# ProPrj_USB_Hub_Port_PCB_2026-08-16.net
KiCad netlist of a schematic drawn in EasyEDA Pro
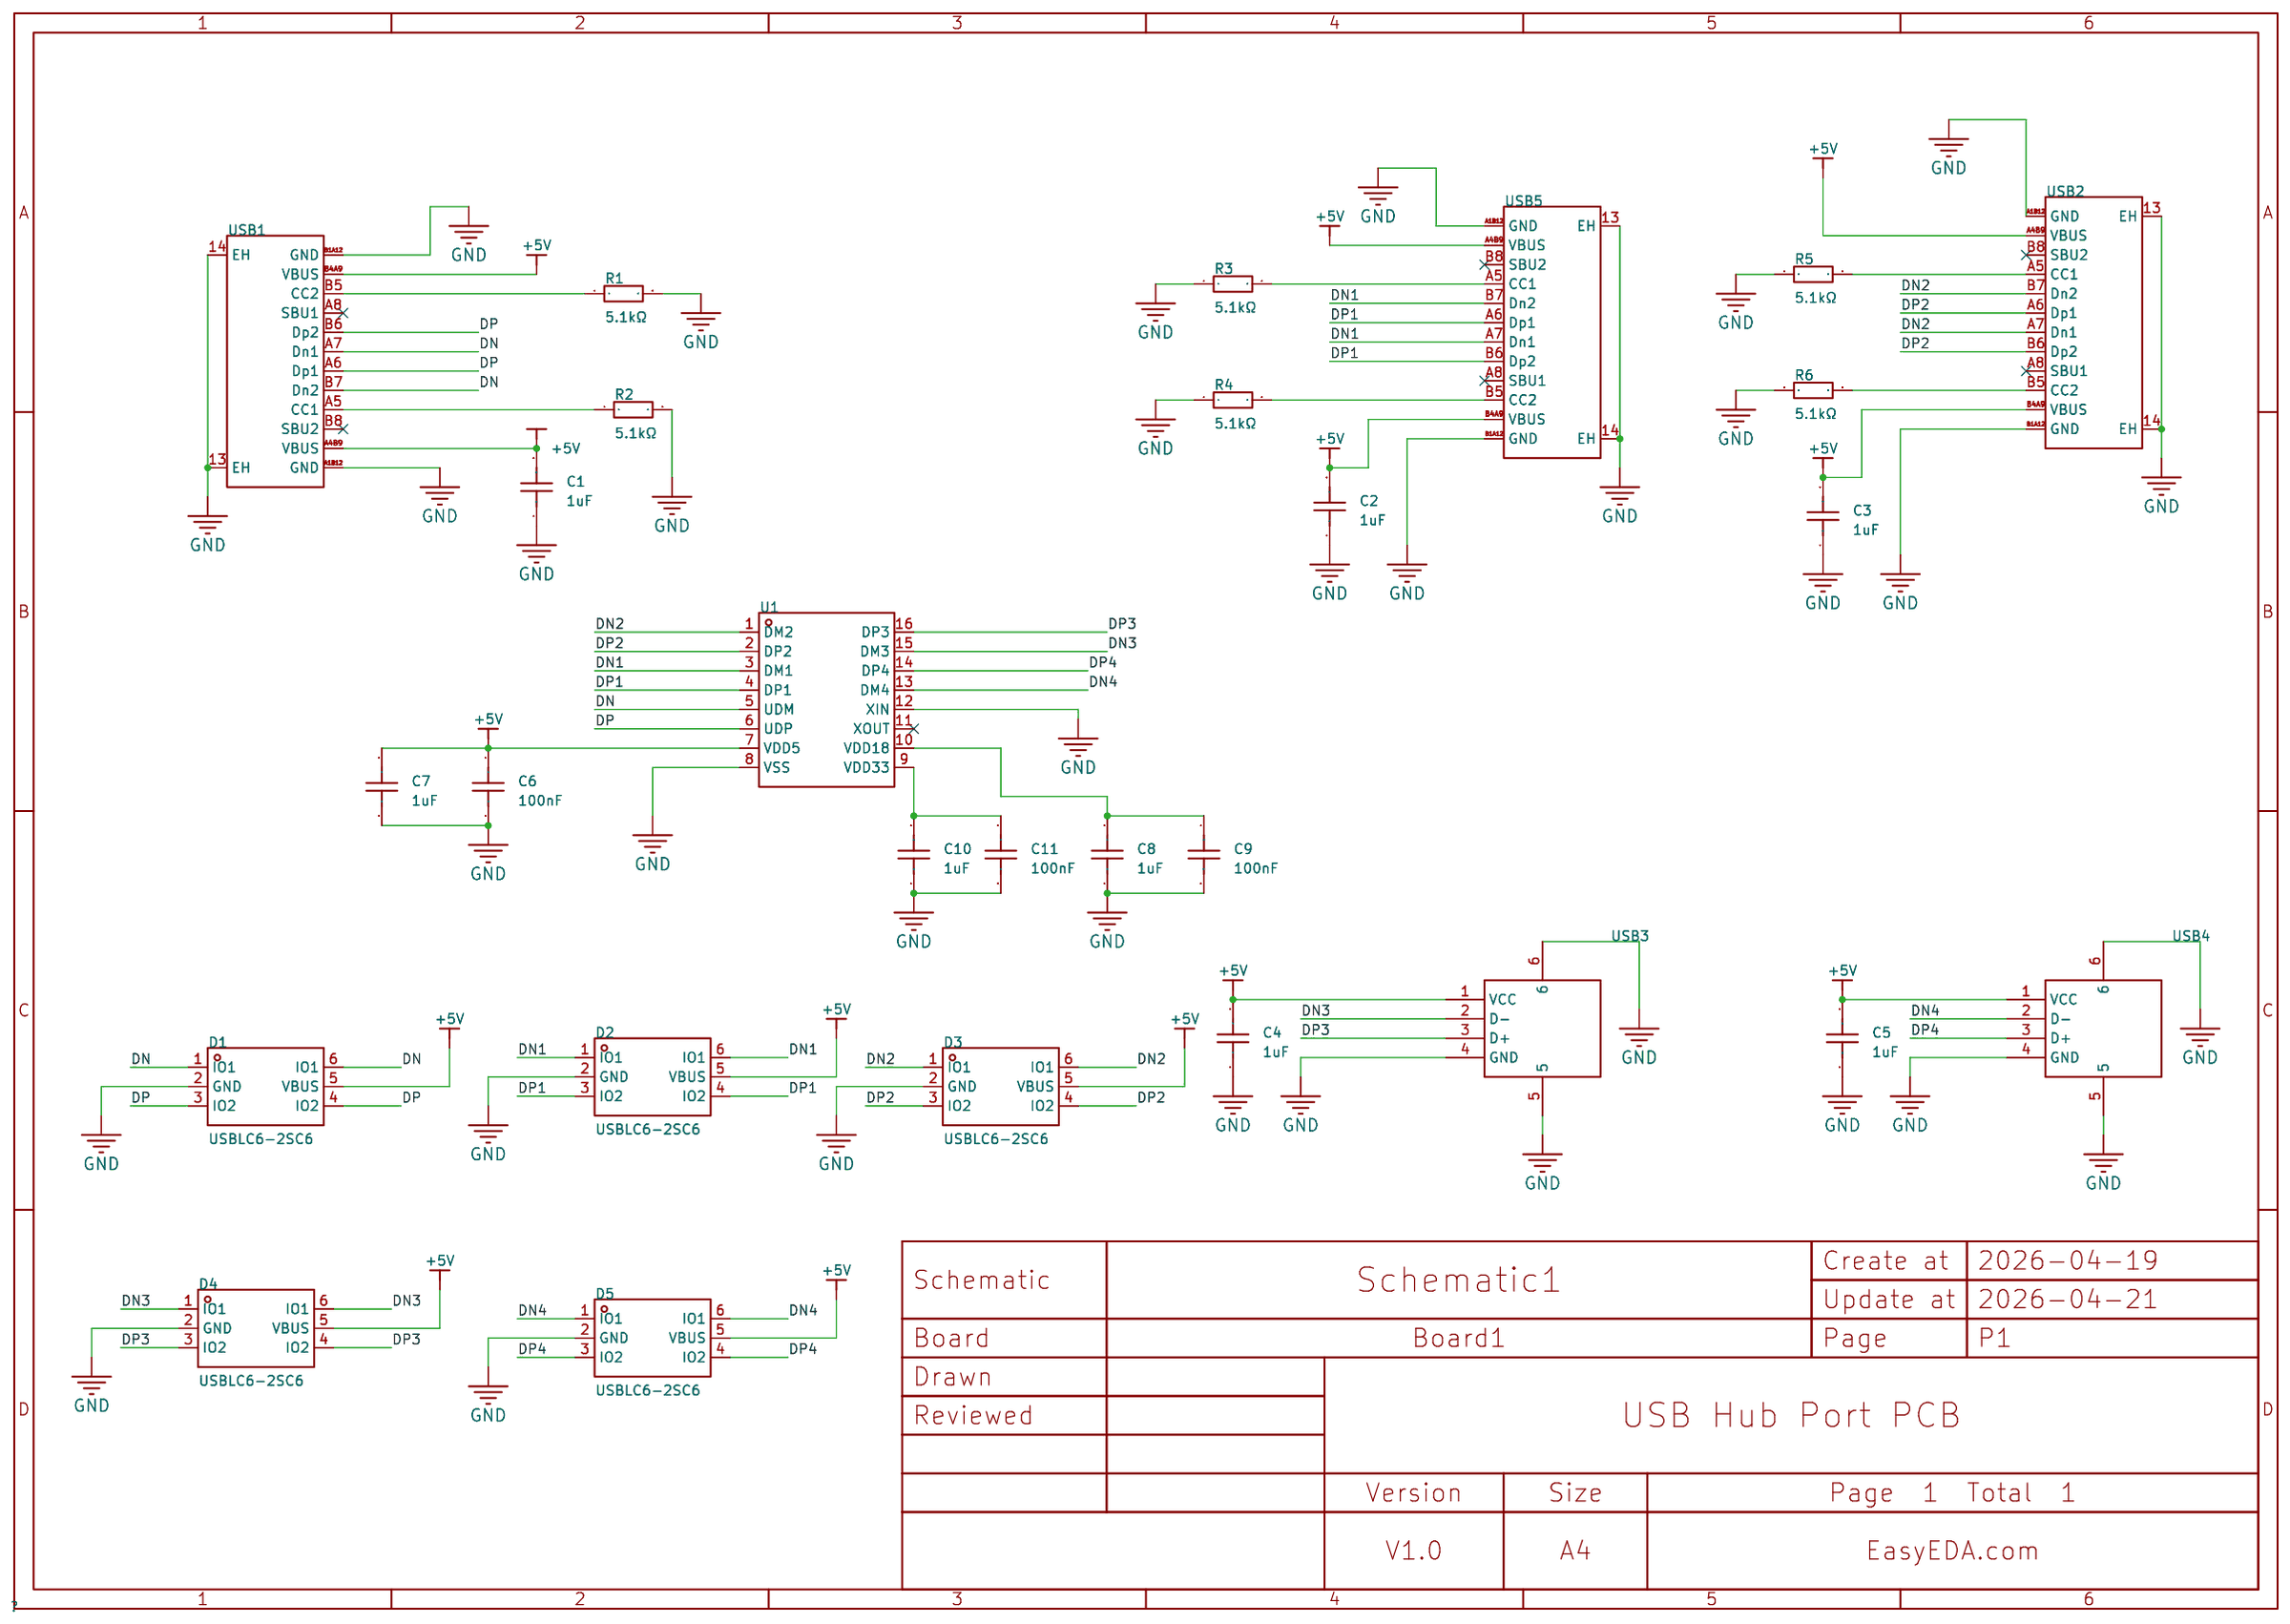
[diagram p0: schematic sheet]

(export (version "E")
  (design (tool "Eeschema 10.0.6"))
  (components
    (comp (ref "C1")
      (value "1uF")
      (footprint "easyedapro:C0603")
      (description "Capacitance:1uF Tolerance:±10% Tolerance:±10% Voltage Rating:50V Temperature Coefficient:X5R")
      (fields
        (field (name "Manufacturer Part") "CL10A105KB8NNNC")
        (field (name "Manufacturer") "SAMSUNG(三星)")
      )
      (libsource (lib "easyedapro") (part "CL10A105KB8NNNC"))
    )
    (comp (ref "C2")
      (value "1uF")
      (footprint "easyedapro:C0603")
      (description "Capacitance:1uF Tolerance:±10% Tolerance:±10% Voltage Rating:50V Temperature Coefficient:X5R")
      (fields
        (field (name "Manufacturer Part") "CL10A105KB8NNNC")
        (field (name "Manufacturer") "SAMSUNG(三星)")
      )
      (libsource (lib "easyedapro") (part "CL10A105KB8NNNC"))
    )
    (comp (ref "C3")
      (value "1uF")
      (footprint "easyedapro:C0603")
      (description "Capacitance:1uF Tolerance:±10% Tolerance:±10% Voltage Rating:50V Temperature Coefficient:X5R")
      (fields
        (field (name "Manufacturer Part") "CL10A105KB8NNNC")
        (field (name "Manufacturer") "SAMSUNG(三星)")
      )
      (libsource (lib "easyedapro") (part "CL10A105KB8NNNC"))
    )
    (comp (ref "C4")
      (value "1uF")
      (footprint "easyedapro:C0603")
      (description "Capacitance:1uF Tolerance:±10% Tolerance:±10% Voltage Rating:50V Temperature Coefficient:X5R")
      (fields
        (field (name "Manufacturer Part") "CL10A105KB8NNNC")
        (field (name "Manufacturer") "SAMSUNG(三星)")
      )
      (libsource (lib "easyedapro") (part "CL10A105KB8NNNC"))
    )
    (comp (ref "C5")
      (value "1uF")
      (footprint "easyedapro:C0603")
      (description "Capacitance:1uF Tolerance:±10% Tolerance:±10% Voltage Rating:50V Temperature Coefficient:X5R")
      (fields
        (field (name "Manufacturer Part") "CL10A105KB8NNNC")
        (field (name "Manufacturer") "SAMSUNG(三星)")
      )
      (libsource (lib "easyedapro") (part "CL10A105KB8NNNC"))
    )
    (comp (ref "C6")
      (value "100nF")
      (footprint "easyedapro:CAP-TH_L7.4-W2.3-P5.08-D0.6")
      (description "Capacitance:100nF Tolerance:±10% Tolerance:±10% Voltage Rating:50V Temperature Coefficient:X7R")
      (fields
        (field (name "Manufacturer Part") "CL10B104KB8NNNC")
        (field (name "Manufacturer") "SAMSUNG(三星)")
      )
      (libsource (lib "easyedapro") (part "CAPR500-350X720X850100NF100V"))
    )
    (comp (ref "C7")
      (value "1uF")
      (footprint "easyedapro:C0603")
      (description "Capacitance:1uF Tolerance:±10% Tolerance:±10% Voltage Rating:50V Temperature Coefficient:X5R")
      (fields
        (field (name "Manufacturer Part") "CL10A105KB8NNNC")
        (field (name "Manufacturer") "SAMSUNG(三星)")
      )
      (libsource (lib "easyedapro") (part "CL10A105KB8NNNC"))
    )
    (comp (ref "C8")
      (value "1uF")
      (footprint "easyedapro:C0603")
      (description "Capacitance:1uF Tolerance:±10% Tolerance:±10% Voltage Rating:50V Temperature Coefficient:X5R")
      (fields
        (field (name "Manufacturer Part") "CL10A105KB8NNNC")
        (field (name "Manufacturer") "SAMSUNG(三星)")
      )
      (libsource (lib "easyedapro") (part "CL10A105KB8NNNC"))
    )
    (comp (ref "C9")
      (value "100nF")
      (footprint "easyedapro:CAP-TH_L7.4-W2.3-P5.08-D0.6")
      (description "Capacitance:100nF Tolerance:±10% Tolerance:±10% Voltage Rating:50V Temperature Coefficient:X7R")
      (fields
        (field (name "Manufacturer Part") "CL10B104KB8NNNC")
        (field (name "Manufacturer") "SAMSUNG(三星)")
      )
      (libsource (lib "easyedapro") (part "CAPR500-350X720X850100NF100V"))
    )
    (comp (ref "C10")
      (value "1uF")
      (footprint "easyedapro:C0603")
      (description "Capacitance:1uF Tolerance:±10% Tolerance:±10% Voltage Rating:50V Temperature Coefficient:X5R")
      (fields
        (field (name "Manufacturer Part") "CL10A105KB8NNNC")
        (field (name "Manufacturer") "SAMSUNG(三星)")
      )
      (libsource (lib "easyedapro") (part "CL10A105KB8NNNC"))
    )
    (comp (ref "C11")
      (value "100nF")
      (footprint "easyedapro:CAP-TH_L7.4-W2.3-P5.08-D0.6")
      (description "Capacitance:100nF Tolerance:±10% Tolerance:±10% Voltage Rating:50V Temperature Coefficient:X7R")
      (fields
        (field (name "Manufacturer Part") "CL10B104KB8NNNC")
        (field (name "Manufacturer") "SAMSUNG(三星)")
      )
      (libsource (lib "easyedapro") (part "CAPR500-350X720X850100NF100V"))
    )
    (comp (ref "D1")
      (value "USBLC6-2SC6")
      (footprint "easyedapro:SOT-23-6_L2.9-W1.6-P0.95-LS2.8-BL")
      (fields (field (name "Manufacturer") "TECH PUBLIC(台舟)"))
      (libsource (lib "easyedapro") (part "USBLC6-2SC6_C2827654"))
    )
    (comp (ref "D2")
      (value "USBLC6-2SC6")
      (footprint "easyedapro:SOT-23-6_L2.9-W1.6-P0.95-LS2.8-BL")
      (fields (field (name "Manufacturer") "TECH PUBLIC(台舟)"))
      (libsource (lib "easyedapro") (part "USBLC6-2SC6_C2827654"))
    )
    (comp (ref "D3")
      (value "USBLC6-2SC6")
      (footprint "easyedapro:SOT-23-6_L2.9-W1.6-P0.95-LS2.8-BL")
      (fields (field (name "Manufacturer") "TECH PUBLIC(台舟)"))
      (libsource (lib "easyedapro") (part "USBLC6-2SC6_C2827654"))
    )
    (comp (ref "D4")
      (value "USBLC6-2SC6")
      (footprint "easyedapro:SOT-23-6_L2.9-W1.6-P0.95-LS2.8-BL")
      (fields (field (name "Manufacturer") "TECH PUBLIC(台舟)"))
      (libsource (lib "easyedapro") (part "USBLC6-2SC6_C2827654"))
    )
    (comp (ref "D5")
      (value "USBLC6-2SC6")
      (footprint "easyedapro:SOT-23-6_L2.9-W1.6-P0.95-LS2.8-BL")
      (fields (field (name "Manufacturer") "TECH PUBLIC(台舟)"))
      (libsource (lib "easyedapro") (part "USBLC6-2SC6_C2827654"))
    )
    (comp (ref "R1")
      (value "5.1kΩ")
      (footprint "easyedapro:R0603")
      (fields
        (field (name "Manufacturer Part") "0603WAF5101T5E")
        (field (name "Manufacturer") "UNI-ROYAL(厚声)")
        (field (name "Tolerance") "±1%")
      )
      (libsource (lib "easyedapro") (part "0603WAF5101T5E"))
    )
    (comp (ref "R2")
      (value "5.1kΩ")
      (footprint "easyedapro:R0603")
      (fields
        (field (name "Manufacturer Part") "0603WAF5101T5E")
        (field (name "Manufacturer") "UNI-ROYAL(厚声)")
        (field (name "Tolerance") "±1%")
      )
      (libsource (lib "easyedapro") (part "0603WAF5101T5E"))
    )
    (comp (ref "R3")
      (value "5.1kΩ")
      (footprint "easyedapro:R0603")
      (fields
        (field (name "Manufacturer Part") "0603WAF5101T5E")
        (field (name "Manufacturer") "UNI-ROYAL(厚声)")
        (field (name "Tolerance") "±1%")
      )
      (libsource (lib "easyedapro") (part "0603WAF5101T5E"))
    )
    (comp (ref "R4")
      (value "5.1kΩ")
      (footprint "easyedapro:R0603")
      (fields
        (field (name "Manufacturer Part") "0603WAF5101T5E")
        (field (name "Manufacturer") "UNI-ROYAL(厚声)")
        (field (name "Tolerance") "±1%")
      )
      (libsource (lib "easyedapro") (part "0603WAF5101T5E"))
    )
    (comp (ref "R5")
      (value "5.1kΩ")
      (footprint "easyedapro:R0603")
      (fields
        (field (name "Manufacturer Part") "0603WAF5101T5E")
        (field (name "Manufacturer") "UNI-ROYAL(厚声)")
        (field (name "Tolerance") "±1%")
      )
      (libsource (lib "easyedapro") (part "0603WAF5101T5E"))
    )
    (comp (ref "R6")
      (value "5.1kΩ")
      (footprint "easyedapro:R0603")
      (fields
        (field (name "Manufacturer Part") "0603WAF5101T5E")
        (field (name "Manufacturer") "UNI-ROYAL(厚声)")
        (field (name "Tolerance") "±1%")
      )
      (libsource (lib "easyedapro") (part "0603WAF5101T5E"))
    )
    (comp (ref "U1")
      (value "SL2.1s")
      (footprint "easyedapro:SSOP-16_L4.6-W2.6-P0.53-LS4.0-BL")
      (fields (field (name "Manufacturer") "CoreChips(和芯润德)"))
      (libsource (lib "easyedapro") (part "SL2.1S"))
    )
    (comp (ref "USB1")
      (value "TYPE-C 16PIN 2MD(073)")
      (footprint "easyedapro:USB-C-SMD_TYPE-C-16PIN-2MD-073")
      (fields (field (name "Manufacturer") "SHOU HAN(首韩)"))
      (libsource (lib "easyedapro") (part "TYPE-C 16PIN 2MD(073)"))
    )
    (comp (ref "USB2")
      (value "TYPE-C 16PIN 2MD(073)")
      (footprint "easyedapro:USB-C-SMD_TYPE-C-16PIN-2MD-073")
      (fields (field (name "Manufacturer") "SHOU HAN(首韩)"))
      (libsource (lib "easyedapro") (part "TYPE-C 16PIN 2MD(073)"))
    )
    (comp (ref "USB3")
      (value "10.0 QHHTZB6.3")
      (footprint "easyedapro:USB-A-TH_10.0QHHTZB6.3")
      (fields (field (name "Manufacturer") "SHOU HAN(首韩)"))
      (libsource (lib "easyedapro") (part "10.0 QHHTZB6.3"))
    )
    (comp (ref "USB4")
      (value "10.0 QHHTZB6.3")
      (footprint "easyedapro:USB-A-TH_10.0QHHTZB6.3")
      (fields (field (name "Manufacturer") "SHOU HAN(首韩)"))
      (libsource (lib "easyedapro") (part "10.0 QHHTZB6.3"))
    )
    (comp (ref "USB5")
      (value "TYPE-C 16PIN 2MD(073)")
      (footprint "easyedapro:USB-C-SMD_TYPE-C-16PIN-2MD-073")
      (fields (field (name "Manufacturer") "SHOU HAN(首韩)"))
      (libsource (lib "easyedapro") (part "TYPE-C 16PIN 2MD(073)"))
    )
  )
  (nets
    (net (code "1") (name "+5V") (class "Default")
      (node (ref "C1") (pin "2") (pinfunction "2_2") (pintype "unspecified"))
      (node (ref "C2") (pin "2") (pinfunction "2_2") (pintype "unspecified"))
      (node (ref "C3") (pin "2") (pinfunction "2_2") (pintype "unspecified"))
      (node (ref "C4") (pin "2") (pinfunction "2_2") (pintype "unspecified"))
      (node (ref "C5") (pin "2") (pinfunction "2_2") (pintype "unspecified"))
      (node (ref "C6") (pin "1") (pinfunction "1_1") (pintype "unspecified"))
      (node (ref "C7") (pin "2") (pinfunction "2_2") (pintype "unspecified"))
      (node (ref "D1") (pin "5") (pinfunction "VBUS_5") (pintype "unspecified"))
      (node (ref "D2") (pin "5") (pinfunction "VBUS_5") (pintype "unspecified"))
      (node (ref "D3") (pin "5") (pinfunction "VBUS_5") (pintype "unspecified"))
      (node (ref "D4") (pin "5") (pinfunction "VBUS_5") (pintype "unspecified"))
      (node (ref "D5") (pin "5") (pinfunction "VBUS_5") (pintype "unspecified"))
      (node (ref "U1") (pin "7") (pinfunction "VDD5_7") (pintype "unspecified"))
      (node (ref "USB1") (pin "A4B9") (pinfunction "VBUS_A4B9") (pintype "unspecified"))
      (node (ref "USB1") (pin "B4A9") (pinfunction "VBUS_B4A9") (pintype "unspecified"))
      (node (ref "USB2") (pin "A4B9") (pinfunction "VBUS_A4B9") (pintype "unspecified"))
      (node (ref "USB2") (pin "B4A9") (pinfunction "VBUS_B4A9") (pintype "unspecified"))
      (node (ref "USB3") (pin "1") (pinfunction "VCC_1") (pintype "unspecified"))
      (node (ref "USB4") (pin "1") (pinfunction "VCC_1") (pintype "unspecified"))
      (node (ref "USB5") (pin "A4B9") (pinfunction "VBUS_A4B9") (pintype "unspecified"))
      (node (ref "USB5") (pin "B4A9") (pinfunction "VBUS_B4A9") (pintype "unspecified"))
    )
    (net (code "2") (name "/DN") (class "Default")
      (node (ref "D1") (pin "1") (pinfunction "IO1_1") (pintype "unspecified"))
      (node (ref "D1") (pin "6") (pinfunction "IO1_6") (pintype "unspecified"))
      (node (ref "U1") (pin "5") (pinfunction "UDM_5") (pintype "unspecified"))
      (node (ref "USB1") (pin "A7") (pinfunction "Dn1_A7") (pintype "unspecified"))
      (node (ref "USB1") (pin "B7") (pinfunction "Dn2_B7") (pintype "unspecified"))
    )
    (net (code "3") (name "/DN1") (class "Default")
      (node (ref "D2") (pin "1") (pinfunction "IO1_1") (pintype "unspecified"))
      (node (ref "D2") (pin "6") (pinfunction "IO1_6") (pintype "unspecified"))
      (node (ref "U1") (pin "3") (pinfunction "DM1_3") (pintype "unspecified"))
      (node (ref "USB5") (pin "A7") (pinfunction "Dn1_A7") (pintype "unspecified"))
      (node (ref "USB5") (pin "B7") (pinfunction "Dn2_B7") (pintype "unspecified"))
    )
    (net (code "4") (name "/DN2") (class "Default")
      (node (ref "D3") (pin "1") (pinfunction "IO1_1") (pintype "unspecified"))
      (node (ref "D3") (pin "6") (pinfunction "IO1_6") (pintype "unspecified"))
      (node (ref "U1") (pin "1") (pinfunction "DM2_1") (pintype "unspecified"))
      (node (ref "USB2") (pin "A7") (pinfunction "Dn1_A7") (pintype "unspecified"))
      (node (ref "USB2") (pin "B7") (pinfunction "Dn2_B7") (pintype "unspecified"))
    )
    (net (code "5") (name "/DN3") (class "Default")
      (node (ref "D4") (pin "1") (pinfunction "IO1_1") (pintype "unspecified"))
      (node (ref "D4") (pin "6") (pinfunction "IO1_6") (pintype "unspecified"))
      (node (ref "U1") (pin "15") (pinfunction "DM3_15") (pintype "unspecified"))
      (node (ref "USB3") (pin "2") (pinfunction "D-_2") (pintype "unspecified"))
    )
    (net (code "6") (name "/DN4") (class "Default")
      (node (ref "D5") (pin "1") (pinfunction "IO1_1") (pintype "unspecified"))
      (node (ref "D5") (pin "6") (pinfunction "IO1_6") (pintype "unspecified"))
      (node (ref "U1") (pin "13") (pinfunction "DM4_13") (pintype "unspecified"))
      (node (ref "USB4") (pin "2") (pinfunction "D-_2") (pintype "unspecified"))
    )
    (net (code "7") (name "/DP") (class "Default")
      (node (ref "D1") (pin "3") (pinfunction "IO2_3") (pintype "unspecified"))
      (node (ref "D1") (pin "4") (pinfunction "IO2_4") (pintype "unspecified"))
      (node (ref "U1") (pin "6") (pinfunction "UDP_6") (pintype "unspecified"))
      (node (ref "USB1") (pin "A6") (pinfunction "Dp1_A6") (pintype "unspecified"))
      (node (ref "USB1") (pin "B6") (pinfunction "Dp2_B6") (pintype "unspecified"))
    )
    (net (code "8") (name "/DP1") (class "Default")
      (node (ref "D2") (pin "3") (pinfunction "IO2_3") (pintype "unspecified"))
      (node (ref "D2") (pin "4") (pinfunction "IO2_4") (pintype "unspecified"))
      (node (ref "U1") (pin "4") (pinfunction "DP1_4") (pintype "unspecified"))
      (node (ref "USB5") (pin "A6") (pinfunction "Dp1_A6") (pintype "unspecified"))
      (node (ref "USB5") (pin "B6") (pinfunction "Dp2_B6") (pintype "unspecified"))
    )
    (net (code "9") (name "/DP2") (class "Default")
      (node (ref "D3") (pin "3") (pinfunction "IO2_3") (pintype "unspecified"))
      (node (ref "D3") (pin "4") (pinfunction "IO2_4") (pintype "unspecified"))
      (node (ref "U1") (pin "2") (pinfunction "DP2_2") (pintype "unspecified"))
      (node (ref "USB2") (pin "A6") (pinfunction "Dp1_A6") (pintype "unspecified"))
      (node (ref "USB2") (pin "B6") (pinfunction "Dp2_B6") (pintype "unspecified"))
    )
    (net (code "10") (name "/DP3") (class "Default")
      (node (ref "D4") (pin "3") (pinfunction "IO2_3") (pintype "unspecified"))
      (node (ref "D4") (pin "4") (pinfunction "IO2_4") (pintype "unspecified"))
      (node (ref "U1") (pin "16") (pinfunction "DP3_16") (pintype "unspecified"))
      (node (ref "USB3") (pin "3") (pinfunction "D+_3") (pintype "unspecified"))
    )
    (net (code "11") (name "/DP4") (class "Default")
      (node (ref "D5") (pin "3") (pinfunction "IO2_3") (pintype "unspecified"))
      (node (ref "D5") (pin "4") (pinfunction "IO2_4") (pintype "unspecified"))
      (node (ref "U1") (pin "14") (pinfunction "DP4_14") (pintype "unspecified"))
      (node (ref "USB4") (pin "3") (pinfunction "D+_3") (pintype "unspecified"))
    )
    (net (code "12") (name "GND") (class "Default")
      (node (ref "C1") (pin "1") (pinfunction "1_1") (pintype "unspecified"))
      (node (ref "C10") (pin "1") (pinfunction "1_1") (pintype "unspecified"))
      (node (ref "C11") (pin "2") (pinfunction "2_2") (pintype "unspecified"))
      (node (ref "C2") (pin "1") (pinfunction "1_1") (pintype "unspecified"))
      (node (ref "C3") (pin "1") (pinfunction "1_1") (pintype "unspecified"))
      (node (ref "C4") (pin "1") (pinfunction "1_1") (pintype "unspecified"))
      (node (ref "C5") (pin "1") (pinfunction "1_1") (pintype "unspecified"))
      (node (ref "C6") (pin "2") (pinfunction "2_2") (pintype "unspecified"))
      (node (ref "C7") (pin "1") (pinfunction "1_1") (pintype "unspecified"))
      (node (ref "C8") (pin "1") (pinfunction "1_1") (pintype "unspecified"))
      (node (ref "C9") (pin "2") (pinfunction "2_2") (pintype "unspecified"))
      (node (ref "D1") (pin "2") (pinfunction "GND_2") (pintype "unspecified"))
      (node (ref "D2") (pin "2") (pinfunction "GND_2") (pintype "unspecified"))
      (node (ref "D3") (pin "2") (pinfunction "GND_2") (pintype "unspecified"))
      (node (ref "D4") (pin "2") (pinfunction "GND_2") (pintype "unspecified"))
      (node (ref "D5") (pin "2") (pinfunction "GND_2") (pintype "unspecified"))
      (node (ref "R1") (pin "2") (pinfunction "2_2") (pintype "input"))
      (node (ref "R2") (pin "2") (pinfunction "2_2") (pintype "input"))
      (node (ref "R3") (pin "1") (pinfunction "1_1") (pintype "input"))
      (node (ref "R4") (pin "1") (pinfunction "1_1") (pintype "input"))
      (node (ref "R5") (pin "1") (pinfunction "1_1") (pintype "input"))
      (node (ref "R6") (pin "1") (pinfunction "1_1") (pintype "input"))
      (node (ref "U1") (pin "12") (pinfunction "XIN_12") (pintype "unspecified"))
      (node (ref "U1") (pin "8") (pinfunction "VSS_8") (pintype "unspecified"))
      (node (ref "USB1") (pin "13") (pinfunction "EH_13") (pintype "unspecified"))
      (node (ref "USB1") (pin "14") (pinfunction "EH_14") (pintype "unspecified"))
      (node (ref "USB1") (pin "A1B12") (pinfunction "GND_A1B12") (pintype "unspecified"))
      (node (ref "USB1") (pin "B1A12") (pinfunction "GND_B1A12") (pintype "unspecified"))
      (node (ref "USB2") (pin "13") (pinfunction "EH_13") (pintype "unspecified"))
      (node (ref "USB2") (pin "14") (pinfunction "EH_14") (pintype "unspecified"))
      (node (ref "USB2") (pin "A1B12") (pinfunction "GND_A1B12") (pintype "unspecified"))
      (node (ref "USB2") (pin "B1A12") (pinfunction "GND_B1A12") (pintype "unspecified"))
      (node (ref "USB3") (pin "4") (pinfunction "GND_4") (pintype "unspecified"))
      (node (ref "USB3") (pin "5") (pinfunction "5_5") (pintype "unspecified"))
      (node (ref "USB3") (pin "6") (pinfunction "6_6") (pintype "unspecified"))
      (node (ref "USB4") (pin "4") (pinfunction "GND_4") (pintype "unspecified"))
      (node (ref "USB4") (pin "5") (pinfunction "5_5") (pintype "unspecified"))
      (node (ref "USB4") (pin "6") (pinfunction "6_6") (pintype "unspecified"))
      (node (ref "USB5") (pin "13") (pinfunction "EH_13") (pintype "unspecified"))
      (node (ref "USB5") (pin "14") (pinfunction "EH_14") (pintype "unspecified"))
      (node (ref "USB5") (pin "A1B12") (pinfunction "GND_A1B12") (pintype "unspecified"))
      (node (ref "USB5") (pin "B1A12") (pinfunction "GND_B1A12") (pintype "unspecified"))
    )
    (net (code "13") (name "Net-(U1-VDD18)") (class "Default")
      (node (ref "C8") (pin "2") (pinfunction "2_2") (pintype "unspecified"))
      (node (ref "C9") (pin "1") (pinfunction "1_1") (pintype "unspecified"))
      (node (ref "U1") (pin "10") (pinfunction "VDD18_10") (pintype "unspecified"))
    )
    (net (code "14") (name "Net-(U1-VDD33)") (class "Default")
      (node (ref "C10") (pin "2") (pinfunction "2_2") (pintype "unspecified"))
      (node (ref "C11") (pin "1") (pinfunction "1_1") (pintype "unspecified"))
      (node (ref "U1") (pin "9") (pinfunction "VDD33_9") (pintype "unspecified"))
    )
    (net (code "15") (name "Net-(USB1-CC1)") (class "Default")
      (node (ref "R2") (pin "1") (pinfunction "1_1") (pintype "input"))
      (node (ref "USB1") (pin "A5") (pinfunction "CC1_A5") (pintype "unspecified"))
    )
    (net (code "16") (name "Net-(USB1-CC2)") (class "Default")
      (node (ref "R1") (pin "1") (pinfunction "1_1") (pintype "input"))
      (node (ref "USB1") (pin "B5") (pinfunction "CC2_B5") (pintype "unspecified"))
    )
    (net (code "17") (name "Net-(USB2-CC1)") (class "Default")
      (node (ref "R5") (pin "2") (pinfunction "2_2") (pintype "input"))
      (node (ref "USB2") (pin "A5") (pinfunction "CC1_A5") (pintype "unspecified"))
    )
    (net (code "18") (name "Net-(USB2-CC2)") (class "Default")
      (node (ref "R6") (pin "2") (pinfunction "2_2") (pintype "input"))
      (node (ref "USB2") (pin "B5") (pinfunction "CC2_B5") (pintype "unspecified"))
    )
    (net (code "19") (name "Net-(USB5-CC1)") (class "Default")
      (node (ref "R3") (pin "2") (pinfunction "2_2") (pintype "input"))
      (node (ref "USB5") (pin "A5") (pinfunction "CC1_A5") (pintype "unspecified"))
    )
    (net (code "20") (name "Net-(USB5-CC2)") (class "Default")
      (node (ref "R4") (pin "2") (pinfunction "2_2") (pintype "input"))
      (node (ref "USB5") (pin "B5") (pinfunction "CC2_B5") (pintype "unspecified"))
    )
    (net (code "21") (name "unconnected-(U1-XOUT-Pad11)") (class "Default")
      (node (ref "U1") (pin "11") (pinfunction "XOUT_11") (pintype "unspecified+no_connect"))
    )
    (net (code "22") (name "unconnected-(USB1-SBU1-PadA8)") (class "Default")
      (node (ref "USB1") (pin "A8") (pinfunction "SBU1_A8") (pintype "unspecified+no_connect"))
    )
    (net (code "23") (name "unconnected-(USB1-SBU2-PadB8)") (class "Default")
      (node (ref "USB1") (pin "B8") (pinfunction "SBU2_B8") (pintype "unspecified+no_connect"))
    )
    (net (code "24") (name "unconnected-(USB2-SBU1-PadA8)") (class "Default")
      (node (ref "USB2") (pin "A8") (pinfunction "SBU1_A8") (pintype "unspecified+no_connect"))
    )
    (net (code "25") (name "unconnected-(USB2-SBU2-PadB8)") (class "Default")
      (node (ref "USB2") (pin "B8") (pinfunction "SBU2_B8") (pintype "unspecified+no_connect"))
    )
    (net (code "26") (name "unconnected-(USB5-SBU1-PadA8)") (class "Default")
      (node (ref "USB5") (pin "A8") (pinfunction "SBU1_A8") (pintype "unspecified+no_connect"))
    )
    (net (code "27") (name "unconnected-(USB5-SBU2-PadB8)") (class "Default")
      (node (ref "USB5") (pin "B8") (pinfunction "SBU2_B8") (pintype "unspecified+no_connect"))
    )
  )
)
